# SCH_SIT210_10_1D_2022-05-21.net
KiCad netlist of a schematic drawn in EasyEDA
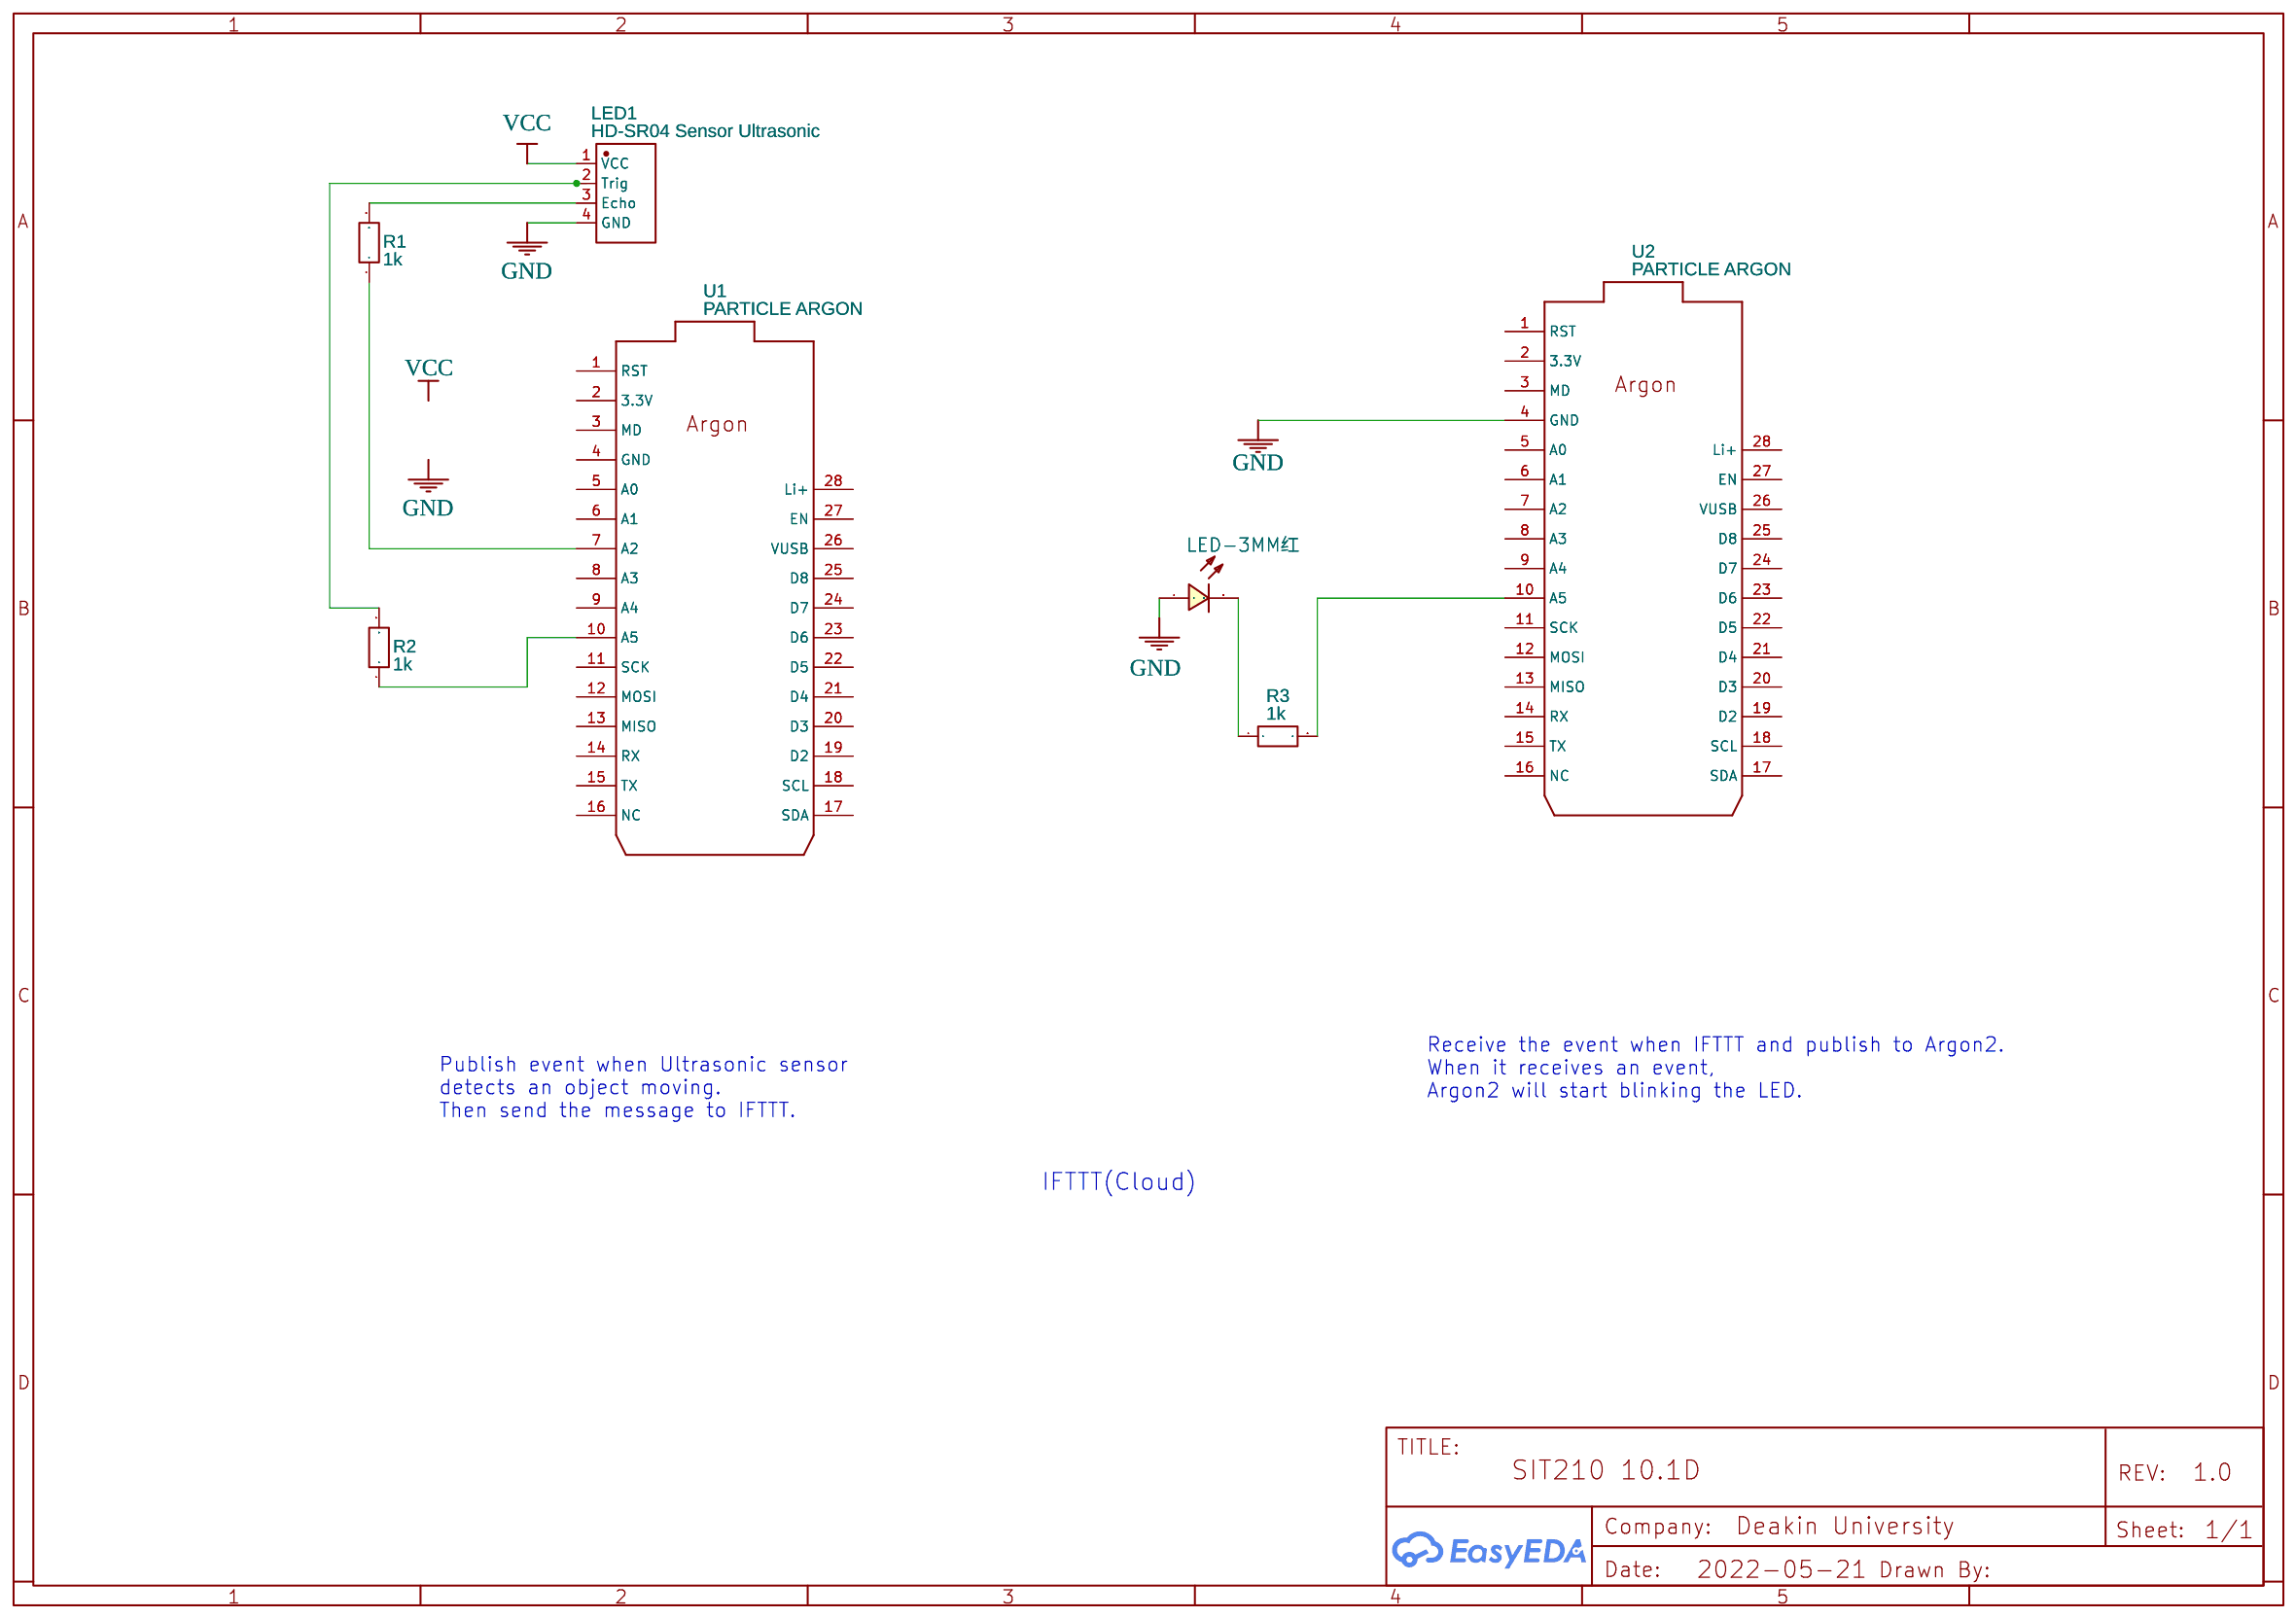
[diagram p0: schematic sheet]

(export (version "E")
  (design (tool "Eeschema 10.0.6"))
  (components
    (comp (ref "LED1")
      (value "HD-SR04 Sensor Ultrasonic")
      (fields
        (field (name "BOM_Manufacturer Part") "TSOP75336TT")
        (field (name "BOM_Supplier Part") "C499577")
      )
      (libsource (lib "") (part "HD-SR04 Sensor Ultrasonic"))
    )
    (comp (ref "NO")
      (value "LED-3MM红")
      (fields
        (field (name "BOM_Manufacturer Part") "LED-3mm红")
        (field (name "BOM_Supplier Part") "C9900003389")
      )
      (libsource (lib "") (part "LED-3MM红"))
    )
    (comp (ref "R1") (value "1k") (libsource (lib "") (part "R_0603_EU")))
    (comp (ref "R2") (value "1k") (libsource (lib "") (part "R_0603_EU")))
    (comp (ref "R3") (value "1k") (libsource (lib "") (part "R_0603_EU_1")))
    (comp (ref "U1")
      (value "PARTICLE ARGON")
      (fields (field (name "BOM_Manufacturer Part") "Particle Argon"))
      (libsource (lib "") (part "PARTICLE ARGON"))
    )
    (comp (ref "U2")
      (value "PARTICLE ARGON")
      (fields (field (name "BOM_Manufacturer Part") "Particle Argon"))
      (libsource (lib "") (part "PARTICLE ARGON"))
    )
  )
  (nets
    (net (code "1") (name "GND") (class "Default")
      (node (ref "LED1") (pin "4") (pinfunction "GND_4") (pintype "unspecified"))
      (node (ref "NO") (pin "1") (pinfunction "1_1") (pintype "unspecified"))
      (node (ref "U2") (pin "4") (pinfunction "GND_4") (pintype "unspecified"))
    )
    (net (code "2") (name "Net-(LED1-Echo)") (class "Default")
      (node (ref "LED1") (pin "3") (pinfunction "Echo_3") (pintype "unspecified"))
      (node (ref "R1") (pin "2") (pinfunction "2_2") (pintype "unspecified"))
    )
    (net (code "3") (name "Net-(LED1-Trig)") (class "Default")
      (node (ref "LED1") (pin "2") (pinfunction "Trig_2") (pintype "unspecified"))
      (node (ref "R2") (pin "2") (pinfunction "2_2") (pintype "unspecified"))
    )
    (net (code "4") (name "Net-(NO-Pad2)") (class "Default")
      (node (ref "NO") (pin "2") (pinfunction "2_2") (pintype "unspecified"))
      (node (ref "R3") (pin "1") (pinfunction "1_1") (pintype "unspecified"))
    )
    (net (code "5") (name "Net-(U1-A2)") (class "Default")
      (node (ref "R1") (pin "1") (pinfunction "1_1") (pintype "unspecified"))
      (node (ref "U1") (pin "7") (pinfunction "A2_7") (pintype "unspecified"))
    )
    (net (code "6") (name "Net-(U1-A5)") (class "Default")
      (node (ref "R2") (pin "1") (pinfunction "1_1") (pintype "unspecified"))
      (node (ref "U1") (pin "10") (pinfunction "A5_10") (pintype "unspecified"))
    )
    (net (code "7") (name "Net-(U2-A5)") (class "Default")
      (node (ref "R3") (pin "2") (pinfunction "2_2") (pintype "unspecified"))
      (node (ref "U2") (pin "10") (pinfunction "A5_10") (pintype "unspecified"))
    )
    (net (code "8") (name "VCC") (class "Default")
      (node (ref "LED1") (pin "1") (pinfunction "VCC_1") (pintype "unspecified"))
    )
    (net (code "9") (name "unconnected-(U1-3.3V-Pad2)") (class "Default")
      (node (ref "U1") (pin "2") (pinfunction "3.3V_2") (pintype "unspecified"))
    )
    (net (code "10") (name "unconnected-(U1-A0-Pad5)") (class "Default")
      (node (ref "U1") (pin "5") (pinfunction "A0_5") (pintype "unspecified"))
    )
    (net (code "11") (name "unconnected-(U1-A1-Pad6)") (class "Default")
      (node (ref "U1") (pin "6") (pinfunction "A1_6") (pintype "unspecified"))
    )
    (net (code "12") (name "unconnected-(U1-A3-Pad8)") (class "Default")
      (node (ref "U1") (pin "8") (pinfunction "A3_8") (pintype "unspecified"))
    )
    (net (code "13") (name "unconnected-(U1-A4-Pad9)") (class "Default")
      (node (ref "U1") (pin "9") (pinfunction "A4_9") (pintype "unspecified"))
    )
    (net (code "14") (name "unconnected-(U1-D2-Pad19)") (class "Default")
      (node (ref "U1") (pin "19") (pinfunction "D2_19") (pintype "unspecified"))
    )
    (net (code "15") (name "unconnected-(U1-D3-Pad20)") (class "Default")
      (node (ref "U1") (pin "20") (pinfunction "D3_20") (pintype "unspecified"))
    )
    (net (code "16") (name "unconnected-(U1-D4-Pad21)") (class "Default")
      (node (ref "U1") (pin "21") (pinfunction "D4_21") (pintype "unspecified"))
    )
    (net (code "17") (name "unconnected-(U1-D5-Pad22)") (class "Default")
      (node (ref "U1") (pin "22") (pinfunction "D5_22") (pintype "unspecified"))
    )
    (net (code "18") (name "unconnected-(U1-D6-Pad23)") (class "Default")
      (node (ref "U1") (pin "23") (pinfunction "D6_23") (pintype "unspecified"))
    )
    (net (code "19") (name "unconnected-(U1-D7-Pad24)") (class "Default")
      (node (ref "U1") (pin "24") (pinfunction "D7_24") (pintype "unspecified"))
    )
    (net (code "20") (name "unconnected-(U1-D8-Pad25)") (class "Default")
      (node (ref "U1") (pin "25") (pinfunction "D8_25") (pintype "unspecified"))
    )
    (net (code "21") (name "unconnected-(U1-EN-Pad27)") (class "Default")
      (node (ref "U1") (pin "27") (pinfunction "EN_27") (pintype "unspecified"))
    )
    (net (code "22") (name "unconnected-(U1-GND-Pad4)") (class "Default")
      (node (ref "U1") (pin "4") (pinfunction "GND_4") (pintype "unspecified"))
    )
    (net (code "23") (name "unconnected-(U1-Li+-Pad28)") (class "Default")
      (node (ref "U1") (pin "28") (pinfunction "Li+_28") (pintype "unspecified"))
    )
    (net (code "24") (name "unconnected-(U1-MD-Pad3)") (class "Default")
      (node (ref "U1") (pin "3") (pinfunction "MD_3") (pintype "unspecified"))
    )
    (net (code "25") (name "unconnected-(U1-MISO-Pad13)") (class "Default")
      (node (ref "U1") (pin "13") (pinfunction "MISO_13") (pintype "unspecified"))
    )
    (net (code "26") (name "unconnected-(U1-MOSI-Pad12)") (class "Default")
      (node (ref "U1") (pin "12") (pinfunction "MOSI_12") (pintype "unspecified"))
    )
    (net (code "27") (name "unconnected-(U1-NC-Pad16)") (class "Default")
      (node (ref "U1") (pin "16") (pinfunction "NC_16") (pintype "unspecified"))
    )
    (net (code "28") (name "unconnected-(U1-RST-Pad1)") (class "Default")
      (node (ref "U1") (pin "1") (pinfunction "RST_1") (pintype "unspecified"))
    )
    (net (code "29") (name "unconnected-(U1-RX-Pad14)") (class "Default")
      (node (ref "U1") (pin "14") (pinfunction "RX_14") (pintype "unspecified"))
    )
    (net (code "30") (name "unconnected-(U1-SCK-Pad11)") (class "Default")
      (node (ref "U1") (pin "11") (pinfunction "SCK_11") (pintype "unspecified"))
    )
    (net (code "31") (name "unconnected-(U1-SCL-Pad18)") (class "Default")
      (node (ref "U1") (pin "18") (pinfunction "SCL_18") (pintype "unspecified"))
    )
    (net (code "32") (name "unconnected-(U1-SDA-Pad17)") (class "Default")
      (node (ref "U1") (pin "17") (pinfunction "SDA_17") (pintype "unspecified"))
    )
    (net (code "33") (name "unconnected-(U1-TX-Pad15)") (class "Default")
      (node (ref "U1") (pin "15") (pinfunction "TX_15") (pintype "unspecified"))
    )
    (net (code "34") (name "unconnected-(U1-VUSB-Pad26)") (class "Default")
      (node (ref "U1") (pin "26") (pinfunction "VUSB_26") (pintype "unspecified"))
    )
    (net (code "35") (name "unconnected-(U2-3.3V-Pad2)") (class "Default")
      (node (ref "U2") (pin "2") (pinfunction "3.3V_2") (pintype "unspecified"))
    )
    (net (code "36") (name "unconnected-(U2-A0-Pad5)") (class "Default")
      (node (ref "U2") (pin "5") (pinfunction "A0_5") (pintype "unspecified"))
    )
    (net (code "37") (name "unconnected-(U2-A1-Pad6)") (class "Default")
      (node (ref "U2") (pin "6") (pinfunction "A1_6") (pintype "unspecified"))
    )
    (net (code "38") (name "unconnected-(U2-A2-Pad7)") (class "Default")
      (node (ref "U2") (pin "7") (pinfunction "A2_7") (pintype "unspecified"))
    )
    (net (code "39") (name "unconnected-(U2-A3-Pad8)") (class "Default")
      (node (ref "U2") (pin "8") (pinfunction "A3_8") (pintype "unspecified"))
    )
    (net (code "40") (name "unconnected-(U2-A4-Pad9)") (class "Default")
      (node (ref "U2") (pin "9") (pinfunction "A4_9") (pintype "unspecified"))
    )
    (net (code "41") (name "unconnected-(U2-D2-Pad19)") (class "Default")
      (node (ref "U2") (pin "19") (pinfunction "D2_19") (pintype "unspecified"))
    )
    (net (code "42") (name "unconnected-(U2-D3-Pad20)") (class "Default")
      (node (ref "U2") (pin "20") (pinfunction "D3_20") (pintype "unspecified"))
    )
    (net (code "43") (name "unconnected-(U2-D4-Pad21)") (class "Default")
      (node (ref "U2") (pin "21") (pinfunction "D4_21") (pintype "unspecified"))
    )
    (net (code "44") (name "unconnected-(U2-D5-Pad22)") (class "Default")
      (node (ref "U2") (pin "22") (pinfunction "D5_22") (pintype "unspecified"))
    )
    (net (code "45") (name "unconnected-(U2-D6-Pad23)") (class "Default")
      (node (ref "U2") (pin "23") (pinfunction "D6_23") (pintype "unspecified"))
    )
    (net (code "46") (name "unconnected-(U2-D7-Pad24)") (class "Default")
      (node (ref "U2") (pin "24") (pinfunction "D7_24") (pintype "unspecified"))
    )
    (net (code "47") (name "unconnected-(U2-D8-Pad25)") (class "Default")
      (node (ref "U2") (pin "25") (pinfunction "D8_25") (pintype "unspecified"))
    )
    (net (code "48") (name "unconnected-(U2-EN-Pad27)") (class "Default")
      (node (ref "U2") (pin "27") (pinfunction "EN_27") (pintype "unspecified"))
    )
    (net (code "49") (name "unconnected-(U2-Li+-Pad28)") (class "Default")
      (node (ref "U2") (pin "28") (pinfunction "Li+_28") (pintype "unspecified"))
    )
    (net (code "50") (name "unconnected-(U2-MD-Pad3)") (class "Default")
      (node (ref "U2") (pin "3") (pinfunction "MD_3") (pintype "unspecified"))
    )
    (net (code "51") (name "unconnected-(U2-MISO-Pad13)") (class "Default")
      (node (ref "U2") (pin "13") (pinfunction "MISO_13") (pintype "unspecified"))
    )
    (net (code "52") (name "unconnected-(U2-MOSI-Pad12)") (class "Default")
      (node (ref "U2") (pin "12") (pinfunction "MOSI_12") (pintype "unspecified"))
    )
    (net (code "53") (name "unconnected-(U2-NC-Pad16)") (class "Default")
      (node (ref "U2") (pin "16") (pinfunction "NC_16") (pintype "unspecified"))
    )
    (net (code "54") (name "unconnected-(U2-RST-Pad1)") (class "Default")
      (node (ref "U2") (pin "1") (pinfunction "RST_1") (pintype "unspecified"))
    )
    (net (code "55") (name "unconnected-(U2-RX-Pad14)") (class "Default")
      (node (ref "U2") (pin "14") (pinfunction "RX_14") (pintype "unspecified"))
    )
    (net (code "56") (name "unconnected-(U2-SCK-Pad11)") (class "Default")
      (node (ref "U2") (pin "11") (pinfunction "SCK_11") (pintype "unspecified"))
    )
    (net (code "57") (name "unconnected-(U2-SCL-Pad18)") (class "Default")
      (node (ref "U2") (pin "18") (pinfunction "SCL_18") (pintype "unspecified"))
    )
    (net (code "58") (name "unconnected-(U2-SDA-Pad17)") (class "Default")
      (node (ref "U2") (pin "17") (pinfunction "SDA_17") (pintype "unspecified"))
    )
    (net (code "59") (name "unconnected-(U2-TX-Pad15)") (class "Default")
      (node (ref "U2") (pin "15") (pinfunction "TX_15") (pintype "unspecified"))
    )
    (net (code "60") (name "unconnected-(U2-VUSB-Pad26)") (class "Default")
      (node (ref "U2") (pin "26") (pinfunction "VUSB_26") (pintype "unspecified"))
    )
  )
)
